# haystack_rgb.net
KiCad netlist of a schematic drawn in EAGLE
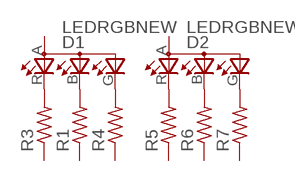
[diagram p0: schematic, sheet 1]

(export (version "E")
  (design (tool "Eeschema 10.0.6"))
  (components
    (comp (ref "D1")
      (value "LEDRGBNEW")
      (footprint "eagle-import:P-LCC-4")
      (libsource (lib "eagle-import") (part "LEDRGBNEW"))
    )
    (comp (ref "D2")
      (value "LEDRGBNEW")
      (footprint "eagle-import:P-LCC-4")
      (libsource (lib "eagle-import") (part "LEDRGBNEW"))
    )
    (comp (ref "R1")
      (value "RES-US1206")
      (footprint "eagle-import:R1206")
      (libsource (lib "eagle-import") (part "RES-US1206"))
    )
    (comp (ref "R3")
      (value "RES-US1206")
      (footprint "eagle-import:R1206")
      (libsource (lib "eagle-import") (part "RES-US1206"))
    )
    (comp (ref "R4")
      (value "RES-US1206")
      (footprint "eagle-import:R1206")
      (libsource (lib "eagle-import") (part "RES-US1206"))
    )
    (comp (ref "R5")
      (value "RES-US1206")
      (footprint "eagle-import:R1206")
      (libsource (lib "eagle-import") (part "RES-US1206"))
    )
    (comp (ref "R6")
      (value "RES-US1206")
      (footprint "eagle-import:R1206")
      (libsource (lib "eagle-import") (part "RES-US1206"))
    )
    (comp (ref "R7")
      (value "RES-US1206")
      (footprint "eagle-import:R1206")
      (libsource (lib "eagle-import") (part "RES-US1206"))
    )
  )
  (nets
    (net (code "1") (name "Net-(D1-CBLUE)") (class "Default")
      (node (ref "D1") (pin "B") (pinfunction "CBLUE_B") (pintype "passive"))
      (node (ref "R1") (pin "2") (pinfunction "2_2") (pintype "passive"))
    )
    (net (code "2") (name "Net-(D1-CGREEN)") (class "Default")
      (node (ref "D1") (pin "G") (pinfunction "CGREEN_G") (pintype "passive"))
      (node (ref "R4") (pin "2") (pinfunction "2_2") (pintype "passive"))
    )
    (net (code "3") (name "Net-(D1-CRED)") (class "Default")
      (node (ref "D1") (pin "R") (pinfunction "CRED_R") (pintype "passive"))
      (node (ref "R3") (pin "2") (pinfunction "2_2") (pintype "passive"))
    )
    (net (code "4") (name "Net-(D2-CBLUE)") (class "Default")
      (node (ref "D2") (pin "B") (pinfunction "CBLUE_B") (pintype "passive"))
      (node (ref "R6") (pin "2") (pinfunction "2_2") (pintype "passive"))
    )
    (net (code "5") (name "Net-(D2-CGREEN)") (class "Default")
      (node (ref "D2") (pin "G") (pinfunction "CGREEN_G") (pintype "passive"))
      (node (ref "R7") (pin "2") (pinfunction "2_2") (pintype "passive"))
    )
    (net (code "6") (name "Net-(D2-CRED)") (class "Default")
      (node (ref "D2") (pin "R") (pinfunction "CRED_R") (pintype "passive"))
      (node (ref "R5") (pin "2") (pinfunction "2_2") (pintype "passive"))
    )
    (net (code "7") (name "unconnected-(D1-A2-PadA)") (class "Default")
      (node (ref "D1") (pin "A") (pinfunction "A2_A") (pintype "passive"))
    )
    (net (code "8") (name "unconnected-(D2-A2-PadA)") (class "Default")
      (node (ref "D2") (pin "A") (pinfunction "A2_A") (pintype "passive"))
    )
    (net (code "9") (name "unconnected-(R1-Pad1)") (class "Default")
      (node (ref "R1") (pin "1") (pinfunction "1_1") (pintype "passive"))
    )
    (net (code "10") (name "unconnected-(R3-Pad1)") (class "Default")
      (node (ref "R3") (pin "1") (pinfunction "1_1") (pintype "passive"))
    )
    (net (code "11") (name "unconnected-(R4-Pad1)") (class "Default")
      (node (ref "R4") (pin "1") (pinfunction "1_1") (pintype "passive"))
    )
    (net (code "12") (name "unconnected-(R5-Pad1)") (class "Default")
      (node (ref "R5") (pin "1") (pinfunction "1_1") (pintype "passive"))
    )
    (net (code "13") (name "unconnected-(R6-Pad1)") (class "Default")
      (node (ref "R6") (pin "1") (pinfunction "1_1") (pintype "passive"))
    )
    (net (code "14") (name "unconnected-(R7-Pad1)") (class "Default")
      (node (ref "R7") (pin "1") (pinfunction "1_1") (pintype "passive"))
    )
  )
)
